# SAME51_PINOUT.net
KiCad netlist of a schematic drawn in Altium Designer
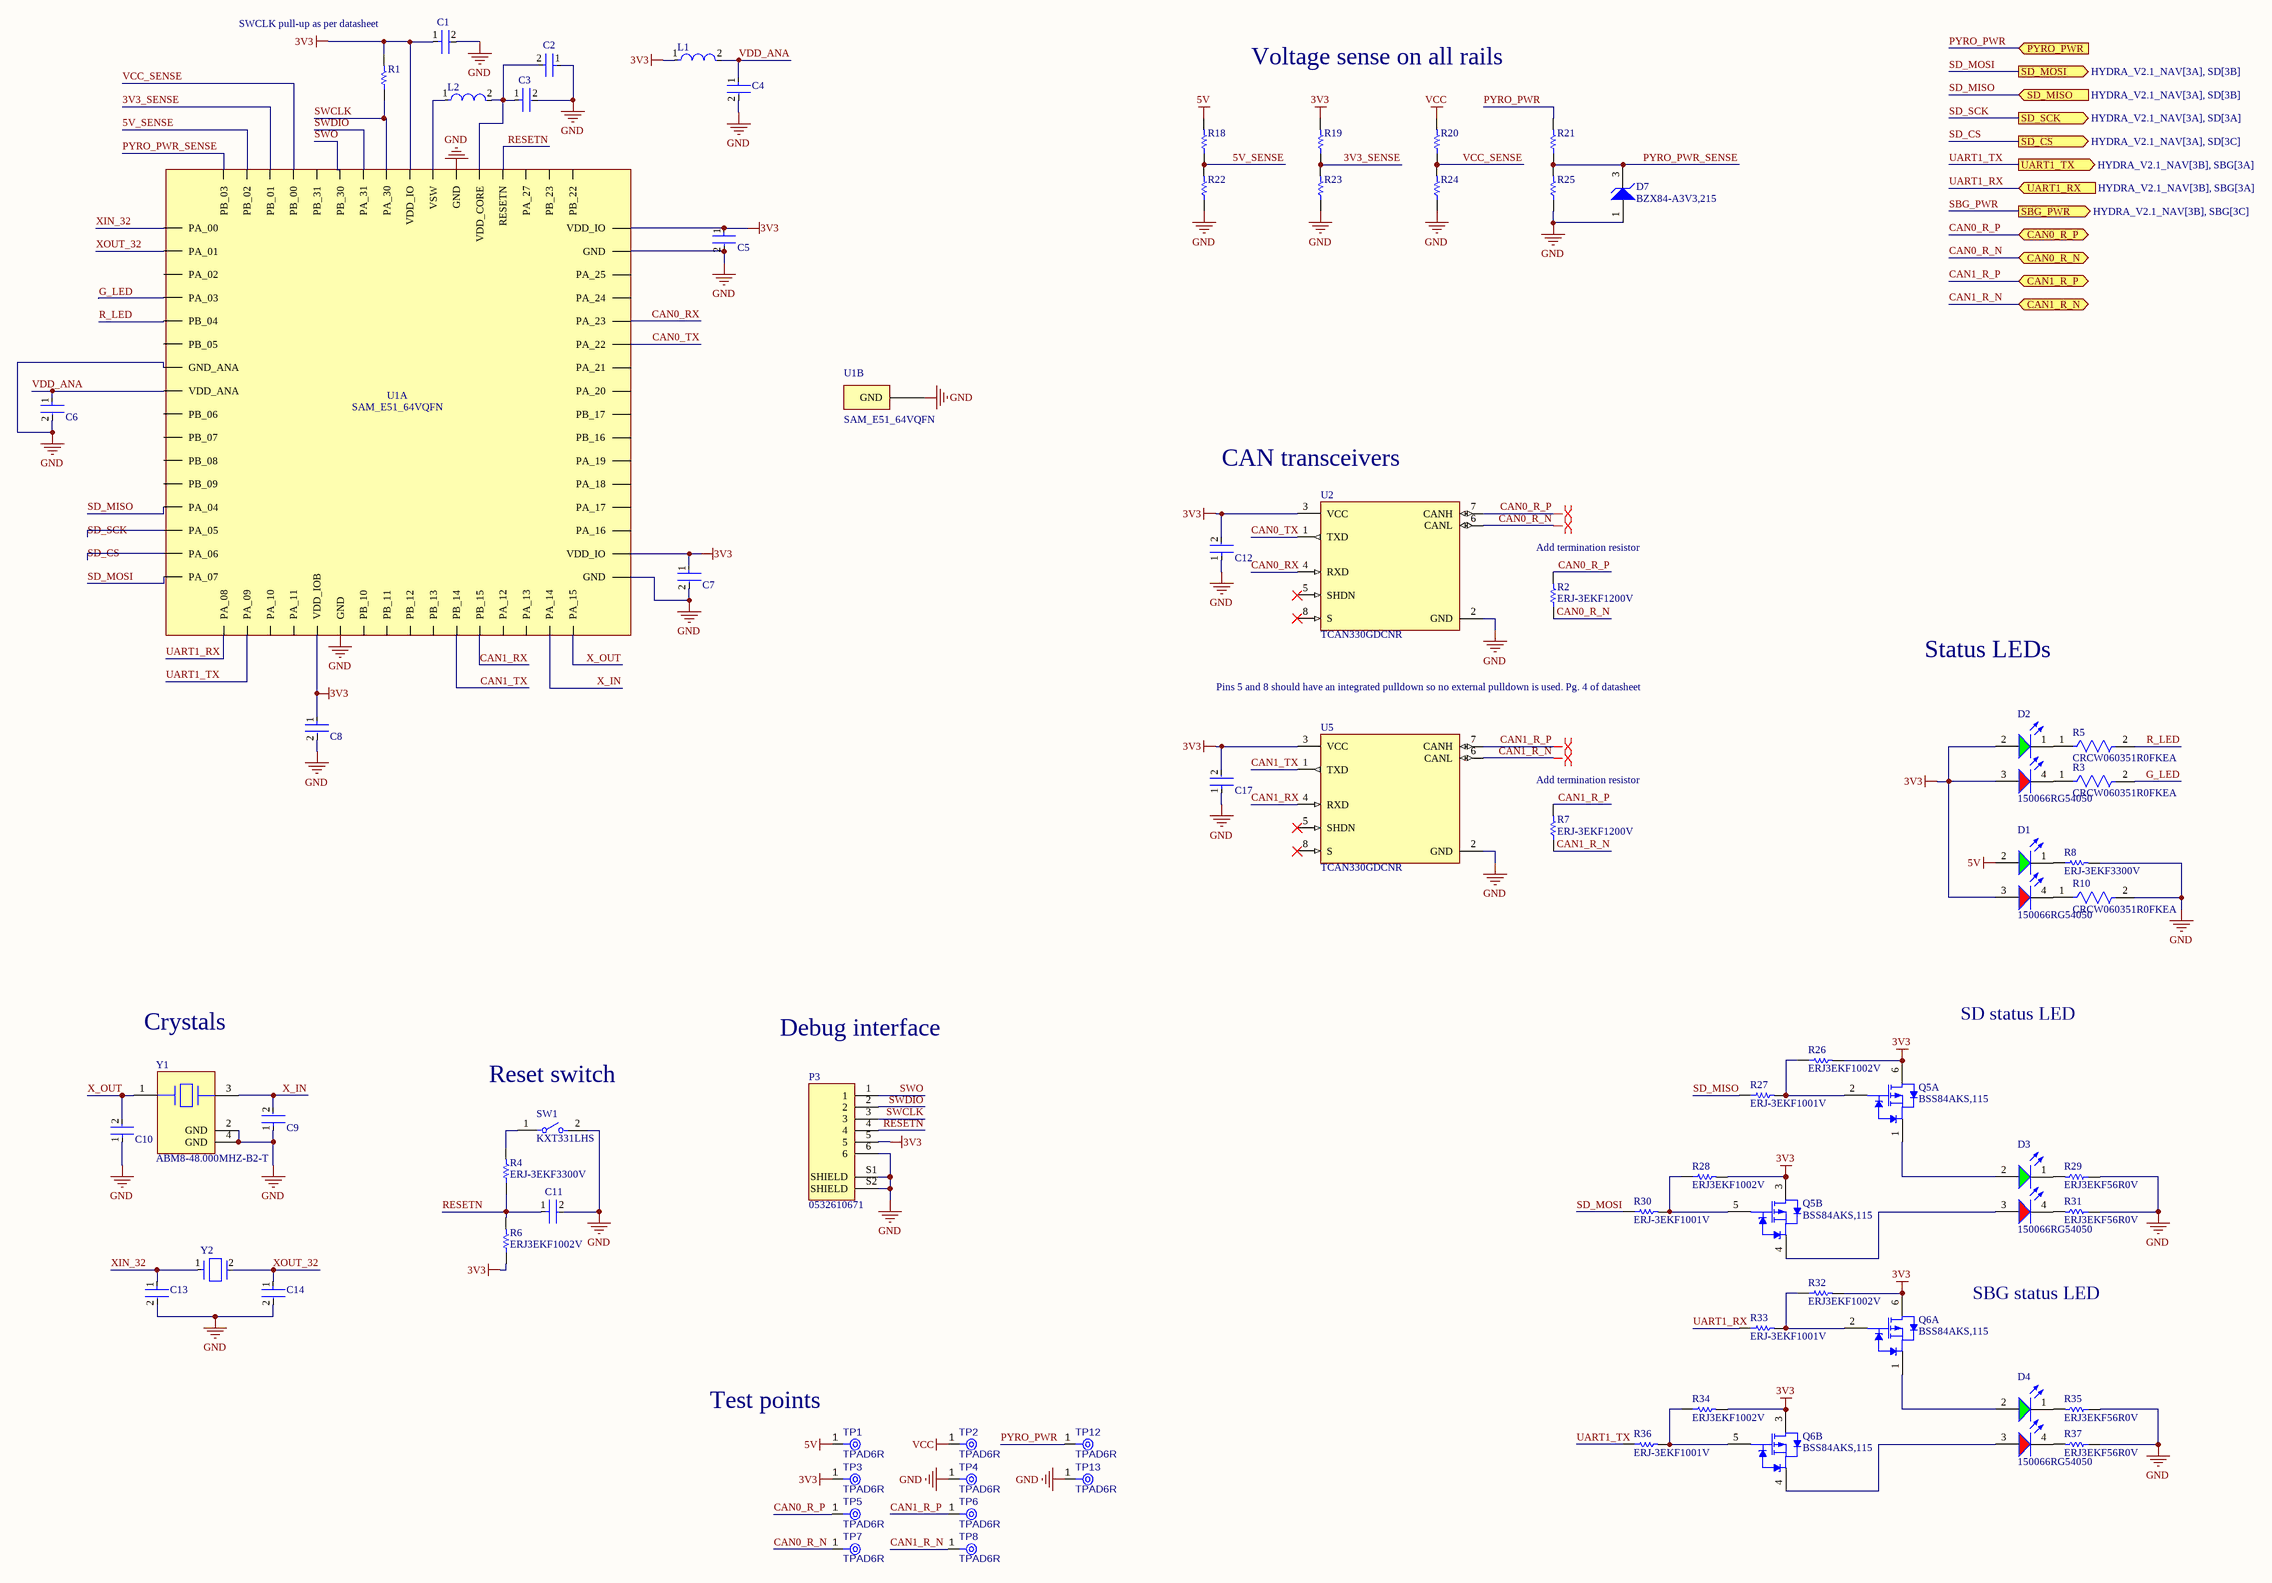
[diagram p0: SAME51_PINOUT.SchDoc]

(export (version "E")
  (design (tool "Eeschema 10.0.6"))
  (components
    (comp (ref "C1")
      (value "C0402C104K8PACTU")
      (footprint "FP-C0402-BB-MFG")
      (description "CAP CER 0.1UF 10V X5R 0402")
      (fields (field (name "MANUFACTURER") "Kemet") (field (name "TOLERANCE") "0.1"))
      (libsource (lib "Altium Content Vault") (part "b4654b650e69147ec39a6b967a45e02"))
    )
    (comp (ref "C2")
      (value "GRM155R60J475ME47D")
      (footprint "FP-GRM155-0_1-IPC_B")
      (description "Chip Multilayer Ceramic Capacitors for General Purpose, 0402, 4.7uF, X5R, 15%, 20%, 6.3V")
      (fields (field (name "VOLTAGE") "6.3V") (field (name "TOLERANCE") "20%"))
      (libsource (lib "Altium Content Vault") (part "11868f565c42a9108669ba33697ecf6"))
    )
    (comp (ref "C3")
      (value "C0402C104K8PACTU")
      (footprint "FP-C0402-BB-MFG")
      (description "CAP CER 0.1UF 10V X5R 0402")
      (fields (field (name "MANUFACTURER") "Kemet") (field (name "TOLERANCE") "0.1"))
      (libsource (lib "Altium Content Vault") (part "b4654b650e69147ec39a6b967a45e02"))
    )
    (comp (ref "C4")
      (value "C0805C106K8PACTU")
      (footprint "FP-C0805C-DG-MFG")
      (description "CAP CER 10UF 10V X5R 0805")
      (fields (field (name "TOLERANCE") "10%") (field (name "MANUFACTURER") "Kemet"))
      (libsource (lib "Altium Content Vault") (part "11868f565c42a9108669ba33697ecf6"))
    )
    (comp (ref "C5")
      (value "C0402C104K8PACTU")
      (footprint "FP-C0402-BB-MFG")
      (description "CAP CER 0.1UF 10V X5R 0402")
      (fields (field (name "MANUFACTURER") "Kemet") (field (name "TOLERANCE") "0.1"))
      (libsource (lib "Altium Content Vault") (part "b4654b650e69147ec39a6b967a45e02"))
    )
    (comp (ref "C6")
      (value "C0402C104K8PACTU")
      (footprint "FP-C0402-BB-MFG")
      (description "CAP CER 0.1UF 10V X5R 0402")
      (fields (field (name "MANUFACTURER") "Kemet") (field (name "TOLERANCE") "0.1"))
      (libsource (lib "Altium Content Vault") (part "b4654b650e69147ec39a6b967a45e02"))
    )
    (comp (ref "C7")
      (value "C0402C104K8PACTU")
      (footprint "FP-C0402-BB-MFG")
      (description "CAP CER 0.1UF 10V X5R 0402")
      (fields (field (name "MANUFACTURER") "Kemet") (field (name "TOLERANCE") "0.1"))
      (libsource (lib "Altium Content Vault") (part "b4654b650e69147ec39a6b967a45e02"))
    )
    (comp (ref "C8")
      (value "C0402C104K8PACTU")
      (footprint "FP-C0402-BB-MFG")
      (description "CAP CER 0.1UF 10V X5R 0402")
      (fields (field (name "MANUFACTURER") "Kemet") (field (name "TOLERANCE") "0.1"))
      (libsource (lib "Altium Content Vault") (part "b4654b650e69147ec39a6b967a45e02"))
    )
    (comp (ref "C9")
      (value "08051A6R8CAT2A")
      (footprint "FP-0805-L_2_01_0_2-W_1_25-MFG")
      (description "General Purpose Ceramic Capacitor, 0805, 6.8pF, 0.25pF, C0G, 30ppm/°C, 100V")
      (fields (field (name "VOLTAGE") "100V") (field (name "TOLERANCE") "5%"))
      (libsource (lib "Altium Content Vault") (part "02cd4be3c70576c341d710602a673aa"))
    )
    (comp (ref "C10")
      (value "08051A6R8CAT2A")
      (footprint "FP-0805-L_2_01_0_2-W_1_25-MFG")
      (description "General Purpose Ceramic Capacitor, 0805, 6.8pF, 0.25pF, C0G, 30ppm/°C, 100V")
      (fields (field (name "VOLTAGE") "100V") (field (name "TOLERANCE") "5%"))
      (libsource (lib "Altium Content Vault") (part "02cd4be3c70576c341d710602a673aa"))
    )
    (comp (ref "C11")
      (value "C0402C104K8PACTU")
      (footprint "FP-C0402-BB-MFG")
      (description "CAP CER 0.1UF 10V X5R 0402")
      (fields (field (name "MANUFACTURER") "Kemet") (field (name "TOLERANCE") "0.1"))
      (libsource (lib "Altium Content Vault") (part "b4654b650e69147ec39a6b967a45e02"))
    )
    (comp (ref "C12")
      (value "C0402C104K8PACTU")
      (footprint "FP-C0402-BB-MFG")
      (description "CAP CER 0.1UF 10V X5R 0402")
      (fields (field (name "MANUFACTURER") "Kemet") (field (name "TOLERANCE") "0.1"))
      (libsource (lib "Altium Content Vault") (part "b4654b650e69147ec39a6b967a45e02"))
    )
    (comp (ref "C13")
      (value "C0805C180J5GACTU")
      (footprint "FP-C0805C-DN-MFG")
      (description "CAP CER 18PF 50V C0G/NP0 0805")
      (fields
        (field (name "OCTOPART") "https://octopart.com/c0805c180j5gactu-kemet-144810")
        (field (name "TOLERANCE") "0.05")
      )
      (libsource (lib "Altium Content Vault") (part "b4654b650e69147ec39a6b967a45e02"))
    )
    (comp (ref "C14")
      (value "C0805C180J5GACTU")
      (footprint "FP-C0805C-DN-MFG")
      (description "CAP CER 18PF 50V C0G/NP0 0805")
      (fields
        (field (name "OCTOPART") "https://octopart.com/c0805c180j5gactu-kemet-144810")
        (field (name "TOLERANCE") "0.05")
      )
      (libsource (lib "Altium Content Vault") (part "b4654b650e69147ec39a6b967a45e02"))
    )
    (comp (ref "C17")
      (value "C0402C104K8PACTU")
      (footprint "FP-C0402-BB-MFG")
      (description "CAP CER 0.1UF 10V X5R 0402")
      (fields (field (name "MANUFACTURER") "Kemet") (field (name "TOLERANCE") "0.1"))
      (libsource (lib "Altium Content Vault") (part "b4654b650e69147ec39a6b967a45e02"))
    )
    (comp (ref "D1")
      (value "150066RG54050")
      (footprint "WL-SBCD_0606")
      (description "Led, Red/Grn, 180Mcd/230Mcd, 624Nm/525Nm Rohs Compliant: Yes")
      (libsource (lib "uORocketry Hardware") (part "WL-SBCD_0606_Red & Green"))
    )
    (comp (ref "D2")
      (value "150066RG54050")
      (footprint "WL-SBCD_0606")
      (description "Led, Red/Grn, 180Mcd/230Mcd, 624Nm/525Nm Rohs Compliant: Yes")
      (libsource (lib "uORocketry Hardware") (part "WL-SBCD_0606_Red & Green"))
    )
    (comp (ref "D3")
      (value "150066RG54050")
      (footprint "WL-SBCD_0606")
      (description "Led, Red/Grn, 180Mcd/230Mcd, 624Nm/525Nm Rohs Compliant: Yes")
      (libsource (lib "uORocketry Hardware") (part "WL-SBCD_0606_Red & Green"))
    )
    (comp (ref "D4")
      (value "150066RG54050")
      (footprint "WL-SBCD_0606")
      (description "Led, Red/Grn, 180Mcd/230Mcd, 624Nm/525Nm Rohs Compliant: Yes")
      (libsource (lib "uORocketry Hardware") (part "WL-SBCD_0606_Red & Green"))
    )
    (comp (ref "D7")
      (value "BZX84-A3V3,215")
      (footprint "SOT95P230X110-3N")
      (description "DIODE ZENER 3.3V 250MW SOT23")
      (libsource (lib "uORocketry Hardware") (part "BZX84-A3V3,215"))
    )
    (comp (ref "L1")
      (value "NR6028T100M")
      (footprint "FP-NR6028-MFG")
      (description "SMD Power Inductors 10uH ±20% 1.9A 84.5mΩ")
      (fields (field (name "TOLERANCE") "20%"))
      (libsource (lib "Altium Content Vault") (part "725321dda6339637d4d059423bc1c3c"))
    )
    (comp (ref "L2")
      (value "NR6028T100M")
      (footprint "FP-NR6028-MFG")
      (description "SMD Power Inductors 10uH ±20% 1.9A 84.5mΩ")
      (fields (field (name "TOLERANCE") "20%"))
      (libsource (lib "Altium Content Vault") (part "725321dda6339637d4d059423bc1c3c"))
    )
    (comp (ref "P3")
      (value "0532610671")
      (footprint "0532610671-Footprint-1")
      (description "Conn Shrouded Header (4 Sides) HDR 6 POS 1.25mm Solder RA Side Entry SMD PicoBlade™ T/R")
      (libsource (lib "uORocketry Hardware") (part "0532610671"))
    )
    (comp (ref "Q5")
      (value "BSS84AKS,115")
      (footprint "NXP-SOT363_L")
      (description "Dual P-Channel Trench MOSFET, -50 V, -0.16 A, -55 to 150 degC, 6-Pin SOT363, Tape and Reel")
      (fields (field (name "MANUFACTURER") "NXP Semiconductors"))
      (libsource (lib "Altium Content Vault") (part "NXP-PPMOS-SGDSGD-6_A"))
    )
    (comp (ref "Q6")
      (value "BSS84AKS,115")
      (footprint "NXP-SOT363_L")
      (description "Dual P-Channel Trench MOSFET, -50 V, -0.16 A, -55 to 150 degC, 6-Pin SOT363, Tape and Reel")
      (fields (field (name "MANUFACTURER") "NXP Semiconductors"))
      (libsource (lib "Altium Content Vault") (part "NXP-PPMOS-SGDSGD-6_A"))
    )
    (comp (ref "R1")
      (value "ERJ3EKF1002V")
      (footprint "RESC1609X55X30LL15T15")
      (description "Chip Resistor, 10 KOhm, +/- 1%, 0.1 W, -55 to 155 degC, 0603 (1608 Metric), RoHS, Tape and Reel")
      (fields (field (name "TOLERANCE") "1%") (field (name "MANUFACTURER") "Panasonic"))
      (libsource (lib "Altium Content Vault") (part "RES-2"))
    )
    (comp (ref "R2")
      (value "ERJ-3EKF1200V")
      (footprint "RESC1609X55X30ML15T15")
      (description "Chip Resistor, 120 Ohm, +/- 1%, 0.1 W, -55 to 155 degC, 0603 (1608 Metric), RoHS, Tape and Reel")
      (fields (field (name "TOLERANCE") "1%") (field (name "MANUFACTURER") "Panasonic"))
      (libsource (lib "Altium Content Vault") (part "RES-2"))
    )
    (comp (ref "R3")
      (value "CRCW060351R0FKEA")
      (footprint "FP-CRCW0603-e3-MFG")
      (description "RES Thick Film, 51Ω, 1%, 0.1W, 100ppm/°C, 0603")
      (fields (field (name "TOLERANCE") "1%"))
      (libsource (lib "Altium Content Vault") (part "1029c3af85768c4190bb7ad29bc67b5"))
    )
    (comp (ref "R4")
      (value "ERJ-3EKF3300V")
      (footprint "RESC1608X55X30LL15T15")
      (description "Chip Resistor, 330 Ohm, +/- 1%, 0.1 W, -55 to 155 degC, 0603 (1608 Metric), RoHS, Tape and Reel")
      (libsource (lib "Altium Content Vault") (part "RES-2"))
    )
    (comp (ref "R5")
      (value "CRCW060351R0FKEA")
      (footprint "FP-CRCW0603-e3-MFG")
      (description "RES Thick Film, 51Ω, 1%, 0.1W, 100ppm/°C, 0603")
      (fields (field (name "TOLERANCE") "1%"))
      (libsource (lib "Altium Content Vault") (part "1029c3af85768c4190bb7ad29bc67b5"))
    )
    (comp (ref "R6")
      (value "ERJ3EKF1002V")
      (footprint "RESC1609X55X30LL15T15")
      (description "Chip Resistor, 10 KOhm, +/- 1%, 0.1 W, -55 to 155 degC, 0603 (1608 Metric), RoHS, Tape and Reel")
      (fields (field (name "TOLERANCE") "1%") (field (name "MANUFACTURER") "Panasonic"))
      (libsource (lib "Altium Content Vault") (part "RES-2"))
    )
    (comp (ref "R7")
      (value "ERJ-3EKF1200V")
      (footprint "RESC1609X55X30ML15T15")
      (description "Chip Resistor, 120 Ohm, +/- 1%, 0.1 W, -55 to 155 degC, 0603 (1608 Metric), RoHS, Tape and Reel")
      (fields (field (name "TOLERANCE") "1%") (field (name "MANUFACTURER") "Panasonic"))
      (libsource (lib "Altium Content Vault") (part "RES-2"))
    )
    (comp (ref "R8")
      (value "ERJ-3EKF3300V")
      (footprint "RESC1608X55X30LL15T15")
      (description "Chip Resistor, 330 Ohm, +/- 1%, 0.1 W, -55 to 155 degC, 0603 (1608 Metric), RoHS, Tape and Reel")
      (libsource (lib "Altium Content Vault") (part "RES-2"))
    )
    (comp (ref "R10")
      (value "CRCW060351R0FKEA")
      (footprint "FP-CRCW0603-e3-MFG")
      (description "RES Thick Film, 51Ω, 1%, 0.1W, 100ppm/°C, 0603")
      (fields (field (name "TOLERANCE") "1%"))
      (libsource (lib "Altium Content Vault") (part "1029c3af85768c4190bb7ad29bc67b5"))
    )
    (comp (ref "R18")
      (value "ERJ3EKF1002V")
      (footprint "RESC1609X55X30LL15T15")
      (description "Chip Resistor, 10 KOhm, +/- 1%, 0.1 W, -55 to 155 degC, 0603 (1608 Metric), RoHS, Tape and Reel")
      (fields (field (name "TOLERANCE") "1%") (field (name "MANUFACTURER") "Panasonic"))
      (libsource (lib "Altium Content Vault") (part "RES-2"))
    )
    (comp (ref "R19")
      (value "ERJ3EKF1002V")
      (footprint "RESC1609X55X30LL15T15")
      (description "Chip Resistor, 10 KOhm, +/- 1%, 0.1 W, -55 to 155 degC, 0603 (1608 Metric), RoHS, Tape and Reel")
      (fields (field (name "TOLERANCE") "1%") (field (name "MANUFACTURER") "Panasonic"))
      (libsource (lib "Altium Content Vault") (part "RES-2"))
    )
    (comp (ref "R20")
      (value "ERJ3EKF1002V")
      (footprint "RESC1609X55X30LL15T15")
      (description "Chip Resistor, 10 KOhm, +/- 1%, 0.1 W, -55 to 155 degC, 0603 (1608 Metric), RoHS, Tape and Reel")
      (fields (field (name "TOLERANCE") "1%") (field (name "MANUFACTURER") "Panasonic"))
      (libsource (lib "Altium Content Vault") (part "RES-2"))
    )
    (comp (ref "R21")
      (value "ERJ3EKF1002V")
      (footprint "RESC1609X55X30LL15T15")
      (description "Chip Resistor, 10 KOhm, +/- 1%, 0.1 W, -55 to 155 degC, 0603 (1608 Metric), RoHS, Tape and Reel")
      (fields (field (name "TOLERANCE") "1%") (field (name "MANUFACTURER") "Panasonic"))
      (libsource (lib "Altium Content Vault") (part "RES-2"))
    )
    (comp (ref "R22")
      (value "ERJ3EKF1002V")
      (footprint "RESC1609X55X30LL15T15")
      (description "Chip Resistor, 10 KOhm, +/- 1%, 0.1 W, -55 to 155 degC, 0603 (1608 Metric), RoHS, Tape and Reel")
      (fields (field (name "TOLERANCE") "1%") (field (name "MANUFACTURER") "Panasonic"))
      (libsource (lib "Altium Content Vault") (part "RES-2"))
    )
    (comp (ref "R23")
      (value "ERJ3EKF1002V")
      (footprint "RESC1609X55X30LL15T15")
      (description "Chip Resistor, 10 KOhm, +/- 1%, 0.1 W, -55 to 155 degC, 0603 (1608 Metric), RoHS, Tape and Reel")
      (fields (field (name "TOLERANCE") "1%") (field (name "MANUFACTURER") "Panasonic"))
      (libsource (lib "Altium Content Vault") (part "RES-2"))
    )
    (comp (ref "R24")
      (value "CRCW06032K70JNEA")
      (footprint "RESC1609X50X30ML10T20")
      (fields (field (name "MANUFACTURER") "Vishay Dale"))
      (libsource (lib "Altium Content Vault") (part "RES"))
    )
    (comp (ref "R25")
      (value "CRCW06032K70JNEA")
      (footprint "RESC1609X50X30ML10T20")
      (fields (field (name "MANUFACTURER") "Vishay Dale"))
      (libsource (lib "Altium Content Vault") (part "RES"))
    )
    (comp (ref "R26")
      (value "ERJ3EKF1002V")
      (footprint "RESC1609X55X30LL15T15")
      (description "Chip Resistor, 10 KOhm, +/- 1%, 0.1 W, -55 to 155 degC, 0603 (1608 Metric), RoHS, Tape and Reel")
      (fields (field (name "TOLERANCE") "1%") (field (name "MANUFACTURER") "Panasonic"))
      (libsource (lib "Altium Content Vault") (part "RES-2"))
    )
    (comp (ref "R27")
      (value "ERJ-3EKF1001V")
      (footprint "RESC1608X55X30LL15T15")
      (fields (field (name "MANUFACTURER") "Panasonic"))
      (libsource (lib "Altium Content Vault") (part "RES"))
    )
    (comp (ref "R28")
      (value "ERJ3EKF1002V")
      (footprint "RESC1609X55X30LL15T15")
      (description "Chip Resistor, 10 KOhm, +/- 1%, 0.1 W, -55 to 155 degC, 0603 (1608 Metric), RoHS, Tape and Reel")
      (fields (field (name "TOLERANCE") "1%") (field (name "MANUFACTURER") "Panasonic"))
      (libsource (lib "Altium Content Vault") (part "RES-2"))
    )
    (comp (ref "R29")
      (value "ERJ3EKF56R0V")
      (footprint "RESC1608X55X30NL15T15")
      (fields (field (name "MANUFACTURER") "Panasonic"))
      (libsource (lib "Altium Content Vault") (part "RES"))
    )
    (comp (ref "R30")
      (value "ERJ-3EKF1001V")
      (footprint "RESC1608X55X30LL15T15")
      (fields (field (name "MANUFACTURER") "Panasonic"))
      (libsource (lib "Altium Content Vault") (part "RES"))
    )
    (comp (ref "R31")
      (value "ERJ3EKF56R0V")
      (footprint "RESC1608X55X30NL15T15")
      (fields (field (name "MANUFACTURER") "Panasonic"))
      (libsource (lib "Altium Content Vault") (part "RES"))
    )
    (comp (ref "R32")
      (value "ERJ3EKF1002V")
      (footprint "RESC1609X55X30LL15T15")
      (description "Chip Resistor, 10 KOhm, +/- 1%, 0.1 W, -55 to 155 degC, 0603 (1608 Metric), RoHS, Tape and Reel")
      (fields (field (name "TOLERANCE") "1%") (field (name "MANUFACTURER") "Panasonic"))
      (libsource (lib "Altium Content Vault") (part "RES-2"))
    )
    (comp (ref "R33")
      (value "ERJ-3EKF1001V")
      (footprint "RESC1608X55X30LL15T15")
      (fields (field (name "MANUFACTURER") "Panasonic"))
      (libsource (lib "Altium Content Vault") (part "RES"))
    )
    (comp (ref "R34")
      (value "ERJ3EKF1002V")
      (footprint "RESC1609X55X30LL15T15")
      (description "Chip Resistor, 10 KOhm, +/- 1%, 0.1 W, -55 to 155 degC, 0603 (1608 Metric), RoHS, Tape and Reel")
      (fields (field (name "TOLERANCE") "1%") (field (name "MANUFACTURER") "Panasonic"))
      (libsource (lib "Altium Content Vault") (part "RES-2"))
    )
    (comp (ref "R35")
      (value "ERJ3EKF56R0V")
      (footprint "RESC1608X55X30NL15T15")
      (fields (field (name "MANUFACTURER") "Panasonic"))
      (libsource (lib "Altium Content Vault") (part "RES"))
    )
    (comp (ref "R36")
      (value "ERJ-3EKF1001V")
      (footprint "RESC1608X55X30LL15T15")
      (fields (field (name "MANUFACTURER") "Panasonic"))
      (libsource (lib "Altium Content Vault") (part "RES"))
    )
    (comp (ref "R37")
      (value "ERJ3EKF56R0V")
      (footprint "RESC1608X55X30NL15T15")
      (fields (field (name "MANUFACTURER") "Panasonic"))
      (libsource (lib "Altium Content Vault") (part "RES"))
    )
    (comp (ref "SW1")
      (value "KXT331LHS")
      (footprint "FP-KXT331LHS-MFG")
      (description "SWITCH TACTILE SPST-NO 0.02A 15V")
      (libsource (lib "Altium Content Vault") (part "bb27bde45df87f1f469753f287ef5ae"))
    )
    (comp (ref "TP1")
      (value "TPAD6R")
      (footprint "TP06R")
      (description "0.6mm round")
      (libsource (lib "uORocketry Hardware") (part "CMP-001-0001-4"))
    )
    (comp (ref "TP2")
      (value "TPAD6R")
      (footprint "TP06R")
      (description "0.6mm round")
      (libsource (lib "uORocketry Hardware") (part "CMP-001-0001-4"))
    )
    (comp (ref "TP3")
      (value "TPAD6R")
      (footprint "TP06R")
      (description "0.6mm round")
      (libsource (lib "uORocketry Hardware") (part "CMP-001-0001-4"))
    )
    (comp (ref "TP4")
      (value "TPAD6R")
      (footprint "TP06R")
      (description "0.6mm round")
      (libsource (lib "uORocketry Hardware") (part "CMP-001-0001-4"))
    )
    (comp (ref "TP5")
      (value "TPAD6R")
      (footprint "TP06R")
      (description "0.6mm round")
      (libsource (lib "uORocketry Hardware") (part "CMP-001-0001-4"))
    )
    (comp (ref "TP6")
      (value "TPAD6R")
      (footprint "TP06R")
      (description "0.6mm round")
      (libsource (lib "uORocketry Hardware") (part "CMP-001-0001-4"))
    )
    (comp (ref "TP7")
      (value "TPAD6R")
      (footprint "TP06R")
      (description "0.6mm round")
      (libsource (lib "uORocketry Hardware") (part "CMP-001-0001-4"))
    )
    (comp (ref "TP8")
      (value "TPAD6R")
      (footprint "TP06R")
      (description "0.6mm round")
      (libsource (lib "uORocketry Hardware") (part "CMP-001-0001-4"))
    )
    (comp (ref "TP12")
      (value "TPAD6R")
      (footprint "TP06R")
      (description "0.6mm round")
      (libsource (lib "uORocketry Hardware") (part "CMP-001-0001-4"))
    )
    (comp (ref "TP13")
      (value "TPAD6R")
      (footprint "TP06R")
      (description "0.6mm round")
      (libsource (lib "uORocketry Hardware") (part "CMP-001-0001-4"))
    )
    (comp (ref "U1")
      (value "SAM_E51_64VQFN")
      (footprint "SAM_E51_64VQFN-Footprint-1")
      (description "Rudimentary symbol and footprint for the SAM E51 microcontroller")
      (libsource (lib "uORocketry Hardware") (part "SAM_E51_64VQFN-Symbol-1"))
    )
    (comp (ref "U2")
      (value "TCAN330GDCNR")
      (footprint "FP-DCN0008A-MFG")
      (description "IC TRANSCEIVER 1/1 SOT23-8")
      (libsource (lib "Altium Content Vault") (part "22681b49c22ad38c6a4e12e04c36c7a"))
    )
    (comp (ref "U5")
      (value "TCAN330GDCNR")
      (footprint "FP-DCN0008A-MFG")
      (description "IC TRANSCEIVER 1/1 SOT23-8")
      (libsource (lib "Altium Content Vault") (part "22681b49c22ad38c6a4e12e04c36c7a"))
    )
    (comp (ref "Y1")
      (value "ABM8-48.000MHZ-B2-T")
      (footprint "FP-ABM8-MFG")
      (description "Crystal 48MHz ±20ppm 18pF SMD-4 3.2mm x 2.5mm")
      (fields (field (name "TOLERANCE") "20ppm"))
      (libsource (lib "Altium Content Vault") (part "dfdb7f9a12507849fb681da9a70121c"))
    )
    (comp (ref "Y2")
      (value "ECS-.327-12.5-1210-TR")
      (footprint "FP-ECX-1210-MFG")
      (description "CRYSTAL 32.7680KHZ 12.5PF SMD")
      (fields
        (field (name "OCTOPART") "https://octopart.com/ecs-.327-12.5-1210-tr-ecs+international-81221340")
        (field (name "TOLERANCE") "20ppm")
      )
      (libsource (lib "Altium Content Vault") (part "99724985039315a44fd0d1401b84e49"))
    )
  )
  (nets
    (net (code "1") (name "/3V3_SENSE") (class "Default")
      (node (ref "R19") (pin "1") (pinfunction "1_1") (pintype "passive"))
      (node (ref "R23") (pin "2") (pinfunction "2_2") (pintype "passive"))
      (node (ref "U1") (pin "62") (pinfunction "PB_01_62") (pintype "passive"))
    )
    (net (code "2") (name "/5V_SENSE") (class "Default")
      (node (ref "R18") (pin "1") (pinfunction "1_1") (pintype "passive"))
      (node (ref "R22") (pin "2") (pinfunction "2_2") (pintype "passive"))
      (node (ref "U1") (pin "63") (pinfunction "PB_02_63") (pintype "passive"))
    )
    (net (code "3") (name "/CAN0_RX") (class "Default")
      (node (ref "U1") (pin "44") (pinfunction "PA_23_44") (pintype "passive"))
      (node (ref "U2") (pin "4") (pinfunction "RXD_4") (pintype "input"))
    )
    (net (code "4") (name "/CAN0_R_N") (class "Default")
      (node (ref "R2") (pin "1") (pinfunction "1_1") (pintype "passive"))
      (node (ref "TP7") (pin "1") (pinfunction "TP_1") (pintype "passive"))
      (node (ref "U2") (pin "6") (pinfunction "CANL_6") (pintype "bidirectional"))
    )
    (net (code "5") (name "/CAN0_R_P") (class "Default")
      (node (ref "R2") (pin "2") (pinfunction "2_2") (pintype "passive"))
      (node (ref "TP5") (pin "1") (pinfunction "TP_1") (pintype "passive"))
      (node (ref "U2") (pin "7") (pinfunction "CANH_7") (pintype "bidirectional"))
    )
    (net (code "6") (name "/CAN0_TX") (class "Default")
      (node (ref "U1") (pin "43") (pinfunction "PA_22_43") (pintype "passive"))
      (node (ref "U2") (pin "1") (pinfunction "TXD_1") (pintype "output"))
    )
    (net (code "7") (name "/CAN1_RX") (class "Default")
      (node (ref "U1") (pin "28") (pinfunction "PB_15_28") (pintype "passive"))
      (node (ref "U5") (pin "4") (pinfunction "RXD_4") (pintype "input"))
    )
    (net (code "8") (name "/CAN1_R_N") (class "Default")
      (node (ref "R7") (pin "1") (pinfunction "1_1") (pintype "passive"))
      (node (ref "TP8") (pin "1") (pinfunction "TP_1") (pintype "passive"))
      (node (ref "U5") (pin "6") (pinfunction "CANL_6") (pintype "bidirectional"))
    )
    (net (code "9") (name "/CAN1_R_P") (class "Default")
      (node (ref "R7") (pin "2") (pinfunction "2_2") (pintype "passive"))
      (node (ref "TP6") (pin "1") (pinfunction "TP_1") (pintype "passive"))
      (node (ref "U5") (pin "7") (pinfunction "CANH_7") (pintype "bidirectional"))
    )
    (net (code "10") (name "/CAN1_TX") (class "Default")
      (node (ref "U1") (pin "27") (pinfunction "PB_14_27") (pintype "passive"))
      (node (ref "U5") (pin "1") (pinfunction "TXD_1") (pintype "output"))
    )
    (net (code "11") (name "/G_LED") (class "Default")
      (node (ref "R3") (pin "2") (pinfunction "2_2") (pintype "passive"))
      (node (ref "U1") (pin "4") (pinfunction "PA_03_4") (pintype "passive"))
    )
    (net (code "12") (name "/PYRO_PWR") (class "Default")
      (node (ref "R21") (pin "2") (pinfunction "2_2") (pintype "passive"))
      (node (ref "TP12") (pin "1") (pinfunction "TP_1") (pintype "passive"))
    )
    (net (code "13") (name "/PYRO_PWR_SENSE") (class "Default")
      (node (ref "D7") (pin "3") (pinfunction "K_3") (pintype "passive"))
      (node (ref "R21") (pin "1") (pinfunction "1_1") (pintype "passive"))
      (node (ref "R25") (pin "2") (pinfunction "2_2") (pintype "passive"))
      (node (ref "U1") (pin "64") (pinfunction "PB_03_64") (pintype "passive"))
    )
    (net (code "14") (name "/RESETN") (class "Default")
      (node (ref "C11") (pin "1") (pinfunction "1_1") (pintype "passive"))
      (node (ref "P3") (pin "4") (pinfunction "4_4") (pintype "passive"))
      (node (ref "R4") (pin "1") (pinfunction "1_1") (pintype "passive"))
      (node (ref "R6") (pin "2") (pinfunction "2_2") (pintype "passive"))
      (node (ref "U1") (pin "52") (pinfunction "RESETN_52") (pintype "passive"))
    )
    (net (code "15") (name "/R_LED") (class "Default")
      (node (ref "R5") (pin "2") (pinfunction "2_2") (pintype "passive"))
      (node (ref "U1") (pin "5") (pinfunction "PB_04_5") (pintype "passive"))
    )
    (net (code "17") (name "/SD_CS") (class "Default")
      (node (ref "U1") (pin "15") (pinfunction "PA_06_15") (pintype "passive"))
    )
    (net (code "18") (name "/SD_MISO") (class "Default")
      (node (ref "R27") (pin "1") (pinfunction "1_1") (pintype "passive"))
      (node (ref "U1") (pin "13") (pinfunction "PA_04_13") (pintype "passive"))
    )
    (net (code "19") (name "/SD_MOSI") (class "Default")
      (node (ref "R30") (pin "1") (pinfunction "1_1") (pintype "passive"))
      (node (ref "U1") (pin "16") (pinfunction "PA_07_16") (pintype "passive"))
    )
    (net (code "20") (name "/SD_SCK") (class "Default")
      (node (ref "U1") (pin "14") (pinfunction "PA_05_14") (pintype "passive"))
    )
    (net (code "21") (name "/SWCLK") (class "Default")
      (node (ref "P3") (pin "3") (pinfunction "3_3") (pintype "passive"))
      (node (ref "R1") (pin "1") (pinfunction "1_1") (pintype "passive"))
      (node (ref "U1") (pin "57") (pinfunction "PA_30_57") (pintype "passive"))
    )
    (net (code "22") (name "/SWDIO") (class "Default")
      (node (ref "P3") (pin "2") (pinfunction "2_2") (pintype "passive"))
      (node (ref "U1") (pin "58") (pinfunction "PA_31_58") (pintype "passive"))
    )
    (net (code "23") (name "/SWO") (class "Default")
      (node (ref "P3") (pin "1") (pinfunction "1_1") (pintype "passive"))
      (node (ref "U1") (pin "59") (pinfunction "PB_30_59") (pintype "passive"))
    )
    (net (code "24") (name "/UART1_RX") (class "Default")
      (node (ref "R33") (pin "1") (pinfunction "1_1") (pintype "passive"))
      (node (ref "U1") (pin "17") (pinfunction "PA_08_17") (pintype "passive"))
    )
    (net (code "25") (name "/UART1_TX") (class "Default")
      (node (ref "R36") (pin "1") (pinfunction "1_1") (pintype "passive"))
      (node (ref "U1") (pin "18") (pinfunction "PA_09_18") (pintype "passive"))
    )
    (net (code "26") (name "/VCC_SENSE") (class "Default")
      (node (ref "R20") (pin "1") (pinfunction "1_1") (pintype "passive"))
      (node (ref "R24") (pin "2") (pinfunction "2_2") (pintype "passive"))
      (node (ref "U1") (pin "61") (pinfunction "PB_00_61") (pintype "passive"))
    )
    (net (code "27") (name "/VDD_ANA") (class "Default")
      (node (ref "C4") (pin "1") (pinfunction "1_1") (pintype "passive"))
      (node (ref "C6") (pin "1") (pinfunction "1_1") (pintype "passive"))
      (node (ref "L1") (pin "2") (pinfunction "2_2") (pintype "passive"))
      (node (ref "U1") (pin "8") (pinfunction "VDD_ANA_8") (pintype "passive"))
    )
    (net (code "28") (name "/XIN_32") (class "Default")
      (node (ref "C13") (pin "1") (pinfunction "1_1") (pintype "passive"))
      (node (ref "U1") (pin "1") (pinfunction "PA_00_1") (pintype "passive"))
      (node (ref "Y2") (pin "1") (pinfunction "In/Out_1") (pintype "passive"))
    )
    (net (code "29") (name "/XOUT_32") (class "Default")
      (node (ref "C14") (pin "1") (pinfunction "1_1") (pintype "passive"))
      (node (ref "U1") (pin "2") (pinfunction "PA_01_2") (pintype "passive"))
      (node (ref "Y2") (pin "2") (pinfunction "Out/In_2") (pintype "passive"))
    )
    (net (code "30") (name "/X_IN") (class "Default")
      (node (ref "C9") (pin "2") (pinfunction "2_2") (pintype "passive"))
      (node (ref "U1") (pin "31") (pinfunction "PA_14_31") (pintype "passive"))
      (node (ref "Y1") (pin "3") (pinfunction "3_3") (pintype "passive"))
    )
    (net (code "31") (name "/X_OUT") (class "Default")
      (node (ref "C10") (pin "2") (pinfunction "2_2") (pintype "passive"))
      (node (ref "U1") (pin "32") (pinfunction "PA_15_32") (pintype "passive"))
      (node (ref "Y1") (pin "1") (pinfunction "1_1") (pintype "passive"))
    )
    (net (code "32") (name "3V3") (class "Default")
      (node (ref "C1") (pin "1") (pinfunction "1_1") (pintype "passive"))
      (node (ref "C12") (pin "2") (pinfunction "2_2") (pintype "passive"))
      (node (ref "C17") (pin "2") (pinfunction "2_2") (pintype "passive"))
      (node (ref "C5") (pin "1") (pinfunction "1_1") (pintype "passive"))
      (node (ref "C7") (pin "1") (pinfunction "1_1") (pintype "passive"))
      (node (ref "C8") (pin "1") (pinfunction "1_1") (pintype "passive"))
      (node (ref "D1") (pin "3") (pinfunction "A_3") (pintype "passive"))
      (node (ref "D2") (pin "2") (pinfunction "A_2") (pintype "passive"))
      (node (ref "D2") (pin "3") (pinfunction "A_3") (pintype "passive"))
      (node (ref "L1") (pin "1") (pinfunction "1_1") (pintype "passive"))
      (node (ref "P3") (pin "5") (pinfunction "5_5") (pintype "passive"))
      (node (ref "Q5") (pin "3") (pinfunction "D2_3") (pintype "passive"))
      (node (ref "Q5") (pin "6") (pinfunction "D1_6") (pintype "passive"))
      (node (ref "Q6") (pin "3") (pinfunction "D2_3") (pintype "passive"))
      (node (ref "Q6") (pin "6") (pinfunction "D1_6") (pintype "passive"))
      (node (ref "R1") (pin "2") (pinfunction "2_2") (pintype "passive"))
      (node (ref "R19") (pin "2") (pinfunction "2_2") (pintype "passive"))
      (node (ref "R26") (pin "2") (pinfunction "2_2") (pintype "passive"))
      (node (ref "R28") (pin "2") (pinfunction "2_2") (pintype "passive"))
      (node (ref "R32") (pin "2") (pinfunction "2_2") (pintype "passive"))
      (node (ref "R34") (pin "2") (pinfunction "2_2") (pintype "passive"))
      (node (ref "R6") (pin "1") (pinfunction "1_1") (pintype "passive"))
      (node (ref "TP3") (pin "1") (pinfunction "TP_1") (pintype "passive"))
      (node (ref "U1") (pin "21") (pinfunction "VDD_IOB_21") (pintype "passive"))
      (node (ref "U1") (pin "34") (pinfunction "VDD_IO_34") (pintype "passive"))
      (node (ref "U1") (pin "48") (pinfunction "VDD_IO_48") (pintype "passive"))
      (node (ref "U1") (pin "56") (pinfunction "VDD_IO_56") (pintype "passive"))
      (node (ref "U2") (pin "3") (pinfunction "VCC_3") (pintype "power_in"))
      (node (ref "U5") (pin "3") (pinfunction "VCC_3") (pintype "power_in"))
    )
    (net (code "33") (name "5V") (class "Default")
      (node (ref "D1") (pin "2") (pinfunction "A_2") (pintype "passive"))
      (node (ref "R18") (pin "2") (pinfunction "2_2") (pintype "passive"))
      (node (ref "TP1") (pin "1") (pinfunction "TP_1") (pintype "passive"))
    )
    (net (code "34") (name "GND") (class "Default")
      (node (ref "C1") (pin "2") (pinfunction "2_2") (pintype "passive"))
      (node (ref "C10") (pin "1") (pinfunction "1_1") (pintype "passive"))
      (node (ref "C11") (pin "2") (pinfunction "2_2") (pintype "passive"))
      (node (ref "C12") (pin "1") (pinfunction "1_1") (pintype "passive"))
      (node (ref "C13") (pin "2") (pinfunction "2_2") (pintype "passive"))
      (node (ref "C14") (pin "2") (pinfunction "2_2") (pintype "passive"))
      (node (ref "C17") (pin "1") (pinfunction "1_1") (pintype "passive"))
      (node (ref "C2") (pin "1") (pinfunction "1_1") (pintype "passive"))
      (node (ref "C3") (pin "2") (pinfunction "2_2") (pintype "passive"))
      (node (ref "C4") (pin "2") (pinfunction "2_2") (pintype "passive"))
      (node (ref "C5") (pin "2") (pinfunction "2_2") (pintype "passive"))
      (node (ref "C6") (pin "2") (pinfunction "2_2") (pintype "passive"))
      (node (ref "C7") (pin "2") (pinfunction "2_2") (pintype "passive"))
      (node (ref "C8") (pin "2") (pinfunction "2_2") (pintype "passive"))
      (node (ref "C9") (pin "1") (pinfunction "1_1") (pintype "passive"))
      (node (ref "D7") (pin "1") (pinfunction "A_1") (pintype "passive"))
      (node (ref "P3") (pin "6") (pinfunction "6_6") (pintype "passive"))
      (node (ref "P3") (pin "S1") (pinfunction "SHIELD_S1") (pintype "passive"))
      (node (ref "P3") (pin "S2") (pinfunction "SHIELD_S2") (pintype "passive"))
      (node (ref "R10") (pin "2") (pinfunction "2_2") (pintype "passive"))
      (node (ref "R22") (pin "1") (pinfunction "1_1") (pintype "passive"))
      (node (ref "R23") (pin "1") (pinfunction "1_1") (pintype "passive"))
      (node (ref "R24") (pin "1") (pinfunction "1_1") (pintype "passive"))
      (node (ref "R25") (pin "1") (pinfunction "1_1") (pintype "passive"))
      (node (ref "R29") (pin "1") (pinfunction "1_1") (pintype "passive"))
      (node (ref "R31") (pin "1") (pinfunction "1_1") (pintype "passive"))
      (node (ref "R35") (pin "1") (pinfunction "1_1") (pintype "passive"))
      (node (ref "R37") (pin "1") (pinfunction "1_1") (pintype "passive"))
      (node (ref "R8") (pin "2") (pinfunction "2_2") (pintype "passive"))
      (node (ref "SW1") (pin "2") (pinfunction "2_2") (pintype "passive"))
      (node (ref "TP13") (pin "1") (pinfunction "TP_1") (pintype "passive"))
      (node (ref "TP4") (pin "1") (pinfunction "TP_1") (pintype "passive"))
      (node (ref "U1") (pin "22") (pinfunction "GND_22") (pintype "passive"))
      (node (ref "U1") (pin "33") (pinfunction "GND_33") (pintype "passive"))
      (node (ref "U1") (pin "47") (pinfunction "GND_47") (pintype "passive"))
      (node (ref "U1") (pin "54") (pinfunction "GND_54") (pintype "passive"))
      (node (ref "U1") (pin "65") (pinfunction "GND_65") (pintype "passive"))
      (node (ref "U1") (pin "7") (pinfunction "GND_ANA_7") (pintype "passive"))
      (node (ref "U2") (pin "2") (pinfunction "GND_2") (pintype "power_in"))
      (node (ref "U5") (pin "2") (pinfunction "GND_2") (pintype "power_in"))
      (node (ref "Y1") (pin "2") (pinfunction "GND_2") (pintype "power_in"))
      (node (ref "Y1") (pin "4") (pinfunction "GND_4") (pintype "power_in"))
    )
    (net (code "35") (name "Net-(D1-K-Pad1)") (class "Default")
      (node (ref "D1") (pin "1") (pinfunction "K_1") (pintype "passive"))
      (node (ref "R8") (pin "1") (pinfunction "1_1") (pintype "passive"))
    )
    (net (code "36") (name "Net-(D1-K-Pad4)") (class "Default")
      (node (ref "D1") (pin "4") (pinfunction "K_4") (pintype "passive"))
      (node (ref "R10") (pin "1") (pinfunction "1_1") (pintype "passive"))
    )
    (net (code "37") (name "Net-(D2-K-Pad1)") (class "Default")
      (node (ref "D2") (pin "1") (pinfunction "K_1") (pintype "passive"))
      (node (ref "R5") (pin "1") (pinfunction "1_1") (pintype "passive"))
    )
    (net (code "38") (name "Net-(D2-K-Pad4)") (class "Default")
      (node (ref "D2") (pin "4") (pinfunction "K_4") (pintype "passive"))
      (node (ref "R3") (pin "1") (pinfunction "1_1") (pintype "passive"))
    )
    (net (code "39") (name "Net-(D3-K-Pad1)") (class "Default")
      (node (ref "D3") (pin "1") (pinfunction "K_1") (pintype "passive"))
      (node (ref "R29") (pin "2") (pinfunction "2_2") (pintype "passive"))
    )
    (net (code "40") (name "Net-(D3-K-Pad4)") (class "Default")
      (node (ref "D3") (pin "4") (pinfunction "K_4") (pintype "passive"))
      (node (ref "R31") (pin "2") (pinfunction "2_2") (pintype "passive"))
    )
    (net (code "41") (name "Net-(D4-K-Pad1)") (class "Default")
      (node (ref "D4") (pin "1") (pinfunction "K_1") (pintype "passive"))
      (node (ref "R35") (pin "2") (pinfunction "2_2") (pintype "passive"))
    )
    (net (code "42") (name "Net-(D4-K-Pad4)") (class "Default")
      (node (ref "D4") (pin "4") (pinfunction "K_4") (pintype "passive"))
      (node (ref "R37") (pin "2") (pinfunction "2_2") (pintype "passive"))
    )
    (net (code "43") (name "Net-(Q5A-G1)") (class "Default")
      (node (ref "Q5") (pin "2") (pinfunction "G1_2") (pintype "passive"))
      (node (ref "R26") (pin "1") (pinfunction "1_1") (pintype "passive"))
      (node (ref "R27") (pin "2") (pinfunction "2_2") (pintype "passive"))
    )
    (net (code "44") (name "Net-(Q5A-S1)") (class "Default")
      (node (ref "D3") (pin "2") (pinfunction "A_2") (pintype "passive"))
      (node (ref "Q5") (pin "1") (pinfunction "S1_1") (pintype "passive"))
    )
    (net (code "45") (name "Net-(Q5B-G2)") (class "Default")
      (node (ref "Q5") (pin "5") (pinfunction "G2_5") (pintype "passive"))
      (node (ref "R28") (pin "1") (pinfunction "1_1") (pintype "passive"))
      (node (ref "R30") (pin "2") (pinfunction "2_2") (pintype "passive"))
    )
    (net (code "46") (name "Net-(Q5B-S2)") (class "Default")
      (node (ref "D3") (pin "3") (pinfunction "A_3") (pintype "passive"))
      (node (ref "Q5") (pin "4") (pinfunction "S2_4") (pintype "passive"))
    )
    (net (code "47") (name "Net-(Q6A-G1)") (class "Default")
      (node (ref "Q6") (pin "2") (pinfunction "G1_2") (pintype "passive"))
      (node (ref "R32") (pin "1") (pinfunction "1_1") (pintype "passive"))
      (node (ref "R33") (pin "2") (pinfunction "2_2") (pintype "passive"))
    )
    (net (code "48") (name "Net-(Q6A-S1)") (class "Default")
      (node (ref "D4") (pin "2") (pinfunction "A_2") (pintype "passive"))
      (node (ref "Q6") (pin "1") (pinfunction "S1_1") (pintype "passive"))
    )
    (net (code "49") (name "Net-(Q6B-G2)") (class "Default")
      (node (ref "Q6") (pin "5") (pinfunction "G2_5") (pintype "passive"))
      (node (ref "R34") (pin "1") (pinfunction "1_1") (pintype "passive"))
      (node (ref "R36") (pin "2") (pinfunction "2_2") (pintype "passive"))
    )
    (net (code "50") (name "Net-(Q6B-S2)") (class "Default")
      (node (ref "D4") (pin "3") (pinfunction "A_3") (pintype "passive"))
      (node (ref "Q6") (pin "4") (pinfunction "S2_4") (pintype "passive"))
    )
    (net (code "51") (name "Net-(R4-Pad2)") (class "Default")
      (node (ref "R4") (pin "2") (pinfunction "2_2") (pintype "passive"))
      (node (ref "SW1") (pin "1") (pinfunction "1_1") (pintype "passive"))
    )
    (net (code "52") (name "Net-(U1A-VDD_CORE)") (class "Default")
      (node (ref "C2") (pin "2") (pinfunction "2_2") (pintype "passive"))
      (node (ref "C3") (pin "1") (pinfunction "1_1") (pintype "passive"))
      (node (ref "L2") (pin "2") (pinfunction "2_2") (pintype "passive"))
      (node (ref "U1") (pin "53") (pinfunction "VDD_CORE_53") (pintype "passive"))
    )
    (net (code "53") (name "Net-(U1A-VSW)") (class "Default")
      (node (ref "L2") (pin "1") (pinfunction "1_1") (pintype "passive"))
      (node (ref "U1") (pin "55") (pinfunction "VSW_55") (pintype "passive"))
    )
    (net (code "54") (name "VCC") (class "Default")
      (node (ref "R20") (pin "2") (pinfunction "2_2") (pintype "passive"))
      (node (ref "TP2") (pin "1") (pinfunction "TP_1") (pintype "passive"))
    )
    (net (code "55") (name "unconnected-(U1A-PA_02-Pad3)") (class "Default")
      (node (ref "U1") (pin "3") (pinfunction "PA_02_3") (pintype "passive"))
    )
    (net (code "56") (name "unconnected-(U1A-PA_10-Pad19)") (class "Default")
      (node (ref "U1") (pin "19") (pinfunction "PA_10_19") (pintype "passive"))
    )
    (net (code "57") (name "unconnected-(U1A-PA_11-Pad20)") (class "Default")
      (node (ref "U1") (pin "20") (pinfunction "PA_11_20") (pintype "passive"))
    )
    (net (code "58") (name "unconnected-(U1A-PA_12-Pad29)") (class "Default")
      (node (ref "U1") (pin "29") (pinfunction "PA_12_29") (pintype "passive"))
    )
    (net (code "59") (name "unconnected-(U1A-PA_13-Pad30)") (class "Default")
      (node (ref "U1") (pin "30") (pinfunction "PA_13_30") (pintype "passive"))
    )
    (net (code "60") (name "unconnected-(U1A-PA_16-Pad35)") (class "Default")
      (node (ref "U1") (pin "35") (pinfunction "PA_16_35") (pintype "passive"))
    )
    (net (code "61") (name "unconnected-(U1A-PA_17-Pad36)") (class "Default")
      (node (ref "U1") (pin "36") (pinfunction "PA_17_36") (pintype "passive"))
    )
    (net (code "62") (name "unconnected-(U1A-PA_18-Pad37)") (class "Default")
      (node (ref "U1") (pin "37") (pinfunction "PA_18_37") (pintype "passive"))
    )
    (net (code "63") (name "unconnected-(U1A-PA_19-Pad38)") (class "Default")
      (node (ref "U1") (pin "38") (pinfunction "PA_19_38") (pintype "passive"))
    )
    (net (code "64") (name "unconnected-(U1A-PA_20-Pad41)") (class "Default")
      (node (ref "U1") (pin "41") (pinfunction "PA_20_41") (pintype "passive"))
    )
    (net (code "65") (name "unconnected-(U1A-PA_21-Pad42)") (class "Default")
      (node (ref "U1") (pin "42") (pinfunction "PA_21_42") (pintype "passive"))
    )
    (net (code "66") (name "unconnected-(U1A-PA_24-Pad45)") (class "Default")
      (node (ref "U1") (pin "45") (pinfunction "PA_24_45") (pintype "passive"))
    )
    (net (code "67") (name "unconnected-(U1A-PA_25-Pad46)") (class "Default")
      (node (ref "U1") (pin "46") (pinfunction "PA_25_46") (pintype "passive"))
    )
    (net (code "68") (name "unconnected-(U1A-PA_27-Pad51)") (class "Default")
      (node (ref "U1") (pin "51") (pinfunction "PA_27_51") (pintype "passive"))
    )
    (net (code "69") (name "unconnected-(U1A-PB_05-Pad6)") (class "Default")
      (node (ref "U1") (pin "6") (pinfunction "PB_05_6") (pintype "passive"))
    )
    (net (code "70") (name "unconnected-(U1A-PB_06-Pad9)") (class "Default")
      (node (ref "U1") (pin "9") (pinfunction "PB_06_9") (pintype "passive"))
    )
    (net (code "71") (name "unconnected-(U1A-PB_07-Pad10)") (class "Default")
      (node (ref "U1") (pin "10") (pinfunction "PB_07_10") (pintype "passive"))
    )
    (net (code "72") (name "unconnected-(U1A-PB_08-Pad11)") (class "Default")
      (node (ref "U1") (pin "11") (pinfunction "PB_08_11") (pintype "passive"))
    )
    (net (code "73") (name "unconnected-(U1A-PB_09-Pad12)") (class "Default")
      (node (ref "U1") (pin "12") (pinfunction "PB_09_12") (pintype "passive"))
    )
    (net (code "74") (name "unconnected-(U1A-PB_10-Pad23)") (class "Default")
      (node (ref "U1") (pin "23") (pinfunction "PB_10_23") (pintype "passive"))
    )
    (net (code "75") (name "unconnected-(U1A-PB_11-Pad24)") (class "Default")
      (node (ref "U1") (pin "24") (pinfunction "PB_11_24") (pintype "passive"))
    )
    (net (code "76") (name "unconnected-(U1A-PB_12-Pad25)") (class "Default")
      (node (ref "U1") (pin "25") (pinfunction "PB_12_25") (pintype "passive"))
    )
    (net (code "77") (name "unconnected-(U1A-PB_13-Pad26)") (class "Default")
      (node (ref "U1") (pin "26") (pinfunction "PB_13_26") (pintype "passive"))
    )
    (net (code "78") (name "unconnected-(U1A-PB_16-Pad39)") (class "Default")
      (node (ref "U1") (pin "39") (pinfunction "PB_16_39") (pintype "passive"))
    )
    (net (code "79") (name "unconnected-(U1A-PB_17-Pad40)") (class "Default")
      (node (ref "U1") (pin "40") (pinfunction "PB_17_40") (pintype "passive"))
    )
    (net (code "80") (name "unconnected-(U1A-PB_22-Pad49)") (class "Default")
      (node (ref "U1") (pin "49") (pinfunction "PB_22_49") (pintype "passive"))
    )
    (net (code "81") (name "unconnected-(U1A-PB_23-Pad50)") (class "Default")
      (node (ref "U1") (pin "50") (pinfunction "PB_23_50") (pintype "passive"))
    )
    (net (code "82") (name "unconnected-(U1A-PB_31-Pad60)") (class "Default")
      (node (ref "U1") (pin "60") (pinfunction "PB_31_60") (pintype "passive"))
    )
    (net (code "83") (name "unconnected-(U2-S-Pad8)") (class "Default")
      (node (ref "U2") (pin "8") (pinfunction "S_8") (pintype "input+no_connect"))
    )
    (net (code "84") (name "unconnected-(U2-SHDN-Pad5)") (class "Default")
      (node (ref "U2") (pin "5") (pinfunction "SHDN_5") (pintype "input+no_connect"))
    )
    (net (code "85") (name "unconnected-(U5-S-Pad8)") (class "Default")
      (node (ref "U5") (pin "8") (pinfunction "S_8") (pintype "input+no_connect"))
    )
    (net (code "86") (name "unconnected-(U5-SHDN-Pad5)") (class "Default")
      (node (ref "U5") (pin "5") (pinfunction "SHDN_5") (pintype "input+no_connect"))
    )
  )
)
